# USB_RF_Gateway_v_0_1.net
KiCad netlist of a schematic drawn in EAGLE
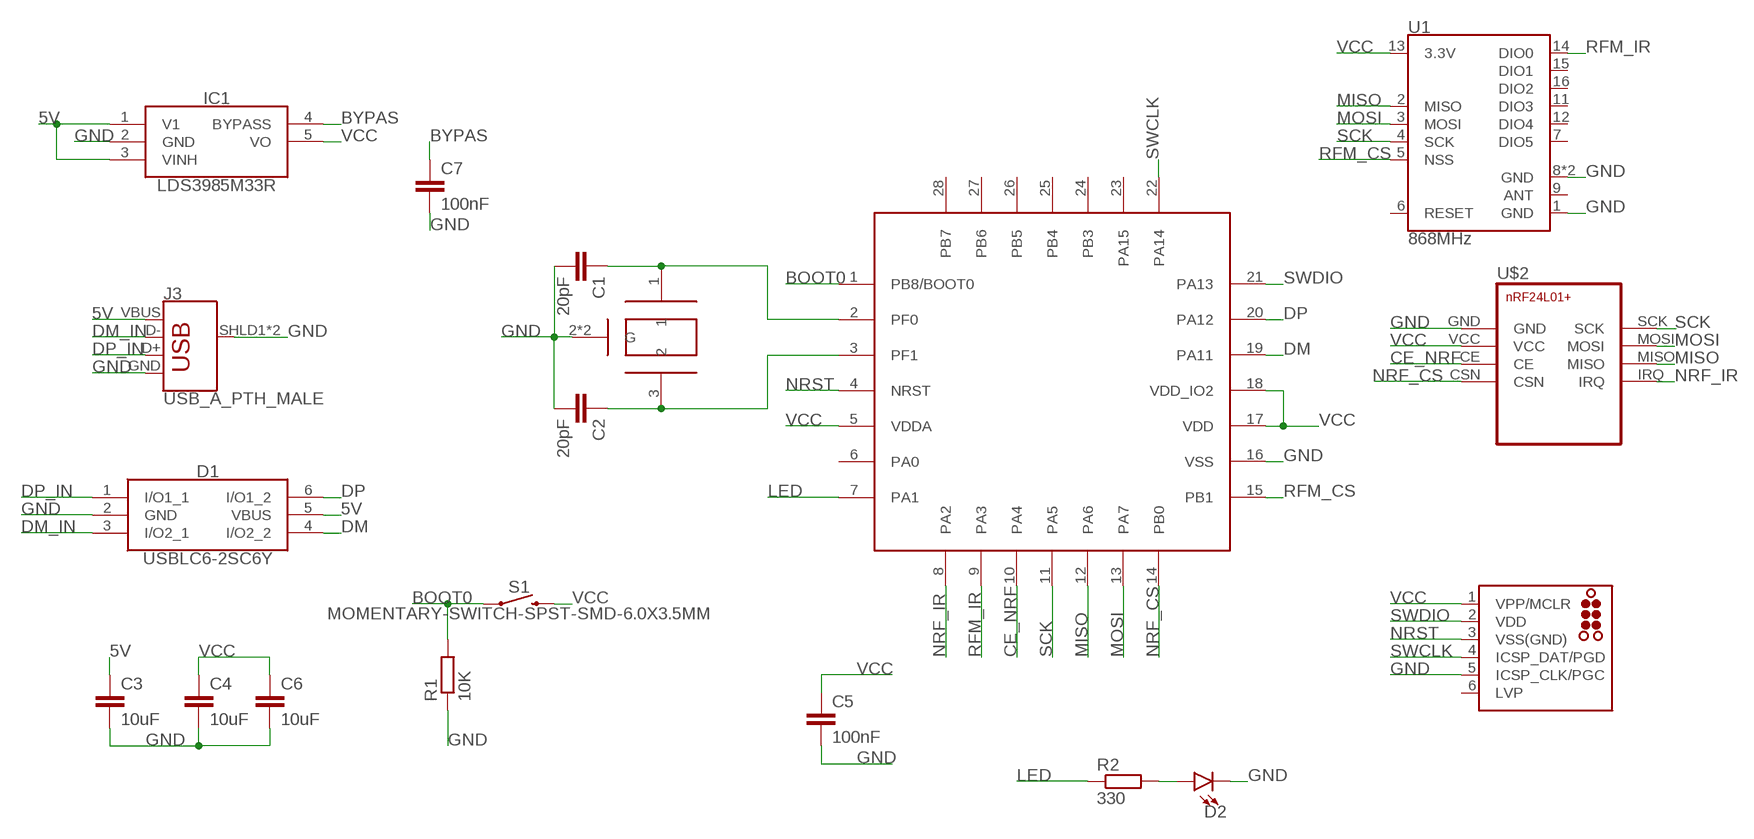
[diagram p0: schematic, sheet 1]

(export (version "E")
  (design (tool "Eeschema 10.0.6"))
  (components
    (comp (ref "C1")
      (value "20pF")
      (footprint "eagle-import:C0603")
      (libsource (lib "eagle-import") (part "C-EUC0603"))
    )
    (comp (ref "C2")
      (value "20pF")
      (footprint "eagle-import:C0603")
      (libsource (lib "eagle-import") (part "C-EUC0603"))
    )
    (comp (ref "C3")
      (value "10uF")
      (footprint "eagle-import:C0805")
      (libsource (lib "eagle-import") (part "C-EUC0805"))
    )
    (comp (ref "C4")
      (value "10uF")
      (footprint "eagle-import:C0805")
      (libsource (lib "eagle-import") (part "C-EUC0805"))
    )
    (comp (ref "C5")
      (value "100nF")
      (footprint "eagle-import:C0603")
      (libsource (lib "eagle-import") (part "C-EUC0603"))
    )
    (comp (ref "C6")
      (value "10uF")
      (footprint "eagle-import:C0805")
      (libsource (lib "eagle-import") (part "C-EUC0805"))
    )
    (comp (ref "C7")
      (value "100nF")
      (footprint "eagle-import:C0603")
      (libsource (lib "eagle-import") (part "C-EUC0603"))
    )
    (comp (ref "D1")
      (value "USBLC6-2SC6Y")
      (footprint "eagle-import:SOT95P280X145-6N")
      (fields
        (field (name "MOUSER_PART_NUMBER") "511-USBLC6-2SC6Y")
        (field (name "RS_PART_NUMBER") "8805525P")
      )
      (libsource (lib "eagle-import") (part "USBLC6-2SC6Y"))
    )
    (comp (ref "D2")
      (value "LED0603")
      (footprint "eagle-import:LED-0603")
      (libsource (lib "eagle-import") (part "LED0603"))
    )
    (comp (ref "IC1")
      (value "LDS3985M33R")
      (footprint "eagle-import:SOT95P280X145-5N")
      (fields
        (field (name "MOUSER_PART_NUMBER") "511-LDS3985M33R")
        (field (name "RS_PART_NUMBER") "8805323P")
      )
      (libsource (lib "eagle-import") (part "LDS3985M33R"))
    )
    (comp (ref "J2")
      (value "TC2030-MCP-NL")
      (footprint "eagle-import:TC2030-MCP-NL")
      (libsource (lib "eagle-import") (part "TC2030-MCP-NL"))
    )
    (comp (ref "J3")
      (value "USB_A_PTH_MALE")
      (footprint "eagle-import:USB-A-H")
      (libsource (lib "eagle-import") (part "USB_A_PTH_MALE"))
    )
    (comp (ref "R1")
      (value "10K")
      (footprint "eagle-import:R0603")
      (libsource (lib "eagle-import") (part "R-EU_R0603"))
    )
    (comp (ref "R2")
      (value "330")
      (footprint "eagle-import:R0603")
      (libsource (lib "eagle-import") (part "R-EU_R0603"))
    )
    (comp (ref "S1")
      (value "MOMENTARY-SWITCH-SPST-SMD-6.0X3.5MM")
      (footprint "eagle-import:TACTILE_SWITCH_SMD_6.0X3.5MM")
      (libsource (lib "eagle-import") (part "MOMENTARY-SWITCH-SPST-SMD-6.0X3.5MM"))
    )
    (comp (ref "U$1")
      (value "ECS-160-12-37B-CTN-TR")
      (footprint "eagle-import:ECS-160-12-37B-CTN")
      (libsource (lib "eagle-import") (part "ECS-160-12-37B-CTN-TR"))
    )
    (comp (ref "U$2")
      (value "NRF24L01+NRF24L01+MINI")
      (footprint "eagle-import:NRF24L01+MINI")
      (libsource (lib "eagle-import") (part "NRF24L01+NRF24L01+MINI"))
    )
    (comp (ref "U$3")
      (value "STMF042G6U6")
      (footprint "eagle-import:STM32F042_UFQPN28_4X4MM")
      (libsource (lib "eagle-import") (part "STMF042G6U6"))
    )
    (comp (ref "U1")
      (value "868MHz")
      (footprint "eagle-import:RFM69HCW-XXXS2")
      (libsource (lib "eagle-import") (part "RFM69HCW-915"))
    )
  )
  (nets
    (net (code "1") (name "/5V") (class "Default")
      (node (ref "C3") (pin "1") (pinfunction "1_1") (pintype "passive"))
      (node (ref "D1") (pin "5") (pinfunction "VBUS_5") (pintype "bidirectional"))
      (node (ref "IC1") (pin "1") (pinfunction "V1_1") (pintype "bidirectional"))
      (node (ref "IC1") (pin "3") (pinfunction "VINH_3") (pintype "bidirectional"))
      (node (ref "J3") (pin "VBUS") (pinfunction "VBUS_VBUS") (pintype "power_in"))
    )
    (net (code "2") (name "/BOOT0") (class "Default")
      (node (ref "R1") (pin "2") (pinfunction "2_2") (pintype "passive"))
      (node (ref "S1") (pin "1") (pinfunction "1_1") (pintype "passive"))
      (node (ref "U$3") (pin "1") (pinfunction "PB8/BOOT0_1") (pintype "bidirectional"))
    )
    (net (code "3") (name "/BYPAS") (class "Default")
      (node (ref "C7") (pin "1") (pinfunction "1_1") (pintype "passive"))
      (node (ref "IC1") (pin "4") (pinfunction "BYPASS_4") (pintype "bidirectional"))
    )
    (net (code "4") (name "/CE_NRF") (class "Default")
      (node (ref "U$2") (pin "CE") (pinfunction "CE_CE") (pintype "bidirectional"))
      (node (ref "U$3") (pin "10") (pinfunction "PA4_10") (pintype "bidirectional"))
    )
    (net (code "5") (name "/DM") (class "Default")
      (node (ref "D1") (pin "4") (pinfunction "I/O2_2_4") (pintype "bidirectional"))
      (node (ref "U$3") (pin "19") (pinfunction "PA11_19") (pintype "bidirectional"))
    )
    (net (code "6") (name "/DM_IN") (class "Default")
      (node (ref "D1") (pin "3") (pinfunction "I/O2_1_3") (pintype "bidirectional"))
      (node (ref "J3") (pin "D-") (pinfunction "D-_D-") (pintype "bidirectional"))
    )
    (net (code "7") (name "/DP") (class "Default")
      (node (ref "D1") (pin "6") (pinfunction "I/O1_2_6") (pintype "bidirectional"))
      (node (ref "U$3") (pin "20") (pinfunction "PA12_20") (pintype "bidirectional"))
    )
    (net (code "8") (name "/DP_IN") (class "Default")
      (node (ref "D1") (pin "1") (pinfunction "I/O1_1_1") (pintype "bidirectional"))
      (node (ref "J3") (pin "D+") (pinfunction "D+_D+") (pintype "bidirectional"))
    )
    (net (code "9") (name "/GND") (class "Default")
      (node (ref "C1") (pin "2") (pinfunction "2_2") (pintype "passive"))
      (node (ref "C2") (pin "2") (pinfunction "2_2") (pintype "passive"))
      (node (ref "C3") (pin "2") (pinfunction "2_2") (pintype "passive"))
      (node (ref "C4") (pin "2") (pinfunction "2_2") (pintype "passive"))
      (node (ref "C5") (pin "2") (pinfunction "2_2") (pintype "passive"))
      (node (ref "C6") (pin "2") (pinfunction "2_2") (pintype "passive"))
      (node (ref "C7") (pin "2") (pinfunction "2_2") (pintype "passive"))
      (node (ref "D1") (pin "2") (pinfunction "GND_2") (pintype "bidirectional"))
      (node (ref "D2") (pin "C") (pinfunction "C_C") (pintype "passive"))
      (node (ref "IC1") (pin "2") (pinfunction "GND_2") (pintype "bidirectional"))
      (node (ref "J2") (pin "5") (pinfunction "ICSP_CLK/PGC_5") (pintype "output"))
      (node (ref "J3") (pin "GND") (pinfunction "GND_GND") (pintype "power_in"))
      (node (ref "J3") (pin "SHLD1") (pinfunction "SHIELD_SHLD1") (pintype "bidirectional"))
      (node (ref "J3") (pin "SHLD2") (pinfunction "SHIELD_SHLD2") (pintype "bidirectional"))
      (node (ref "R1") (pin "1") (pinfunction "1_1") (pintype "passive"))
      (node (ref "U$1") (pin "2") (pinfunction "G_2") (pintype "bidirectional"))
      (node (ref "U$1") (pin "4") (pinfunction "G_4") (pintype "bidirectional"))
      (node (ref "U$2") (pin "GND") (pinfunction "GND_GND") (pintype "power_in"))
      (node (ref "U$3") (pin "16") (pinfunction "VSS_16") (pintype "bidirectional"))
      (node (ref "U1") (pin "1") (pinfunction "GND_1") (pintype "power_in"))
      (node (ref "U1") (pin "10") (pinfunction "GND_10") (pintype "power_in"))
      (node (ref "U1") (pin "8") (pinfunction "GND_8") (pintype "power_in"))
    )
    (net (code "10") (name "/LED") (class "Default")
      (node (ref "R2") (pin "1") (pinfunction "1_1") (pintype "passive"))
      (node (ref "U$3") (pin "7") (pinfunction "PA1_7") (pintype "bidirectional"))
    )
    (net (code "11") (name "/MISO") (class "Default")
      (node (ref "U$2") (pin "MISO") (pinfunction "MISO_MISO") (pintype "bidirectional"))
      (node (ref "U$3") (pin "12") (pinfunction "PA6_12") (pintype "bidirectional"))
      (node (ref "U1") (pin "2") (pinfunction "MISO_2") (pintype "bidirectional"))
    )
    (net (code "12") (name "/MOSI") (class "Default")
      (node (ref "U$2") (pin "MOSI") (pinfunction "MOSI_MOSI") (pintype "bidirectional"))
      (node (ref "U$3") (pin "13") (pinfunction "PA7_13") (pintype "bidirectional"))
      (node (ref "U1") (pin "3") (pinfunction "MOSI_3") (pintype "input"))
    )
    (net (code "13") (name "/NRF_CS") (class "Default")
      (node (ref "U$2") (pin "CSN") (pinfunction "CSN_CSN") (pintype "bidirectional"))
      (node (ref "U$3") (pin "14") (pinfunction "PB0_14") (pintype "bidirectional"))
    )
    (net (code "14") (name "/NRF_IR") (class "Default")
      (node (ref "U$2") (pin "IRQ") (pinfunction "IRQ_IRQ") (pintype "bidirectional"))
      (node (ref "U$3") (pin "8") (pinfunction "PA2_8") (pintype "bidirectional"))
    )
    (net (code "15") (name "/NRST") (class "Default")
      (node (ref "J2") (pin "3") (pinfunction "VSS(GND)_3") (pintype "power_in"))
      (node (ref "U$3") (pin "4") (pinfunction "NRST_4") (pintype "bidirectional"))
    )
    (net (code "16") (name "/RFM_CS") (class "Default")
      (node (ref "U$3") (pin "15") (pinfunction "PB1_15") (pintype "bidirectional"))
      (node (ref "U1") (pin "5") (pinfunction "NSS_5") (pintype "input"))
    )
    (net (code "17") (name "/RFM_IR") (class "Default")
      (node (ref "U$3") (pin "9") (pinfunction "PA3_9") (pintype "bidirectional"))
      (node (ref "U1") (pin "14") (pinfunction "DIO0_14") (pintype "bidirectional"))
    )
    (net (code "18") (name "/SCK") (class "Default")
      (node (ref "U$2") (pin "SCK") (pinfunction "SCK_SCK") (pintype "bidirectional"))
      (node (ref "U$3") (pin "11") (pinfunction "PA5_11") (pintype "bidirectional"))
      (node (ref "U1") (pin "4") (pinfunction "SCK_4") (pintype "input"))
    )
    (net (code "19") (name "/SWCLK") (class "Default")
      (node (ref "J2") (pin "4") (pinfunction "ICSP_DAT/PGD_4") (pintype "bidirectional"))
      (node (ref "U$3") (pin "22") (pinfunction "PA14_22") (pintype "bidirectional"))
    )
    (net (code "20") (name "/SWDIO") (class "Default")
      (node (ref "J2") (pin "2") (pinfunction "VDD_2") (pintype "power_in"))
      (node (ref "U$3") (pin "21") (pinfunction "PA13_21") (pintype "bidirectional"))
    )
    (net (code "21") (name "/VCC") (class "Default")
      (node (ref "C4") (pin "1") (pinfunction "1_1") (pintype "passive"))
      (node (ref "C5") (pin "1") (pinfunction "1_1") (pintype "passive"))
      (node (ref "C6") (pin "1") (pinfunction "1_1") (pintype "passive"))
      (node (ref "IC1") (pin "5") (pinfunction "VO_5") (pintype "bidirectional"))
      (node (ref "J2") (pin "1") (pinfunction "VPP/MCLR_1") (pintype "passive"))
      (node (ref "S1") (pin "2") (pinfunction "2_2") (pintype "passive"))
      (node (ref "U$2") (pin "VCC") (pinfunction "VCC_VCC") (pintype "power_in"))
      (node (ref "U$3") (pin "17") (pinfunction "VDD_17") (pintype "bidirectional"))
      (node (ref "U$3") (pin "18") (pinfunction "VDD_IO2_18") (pintype "bidirectional"))
      (node (ref "U$3") (pin "5") (pinfunction "VDDA_5") (pintype "bidirectional"))
      (node (ref "U1") (pin "13") (pinfunction "3.3V_13") (pintype "power_in"))
    )
    (net (code "22") (name "Net-(D2-PadA)") (class "Default")
      (node (ref "D2") (pin "A") (pinfunction "A_A") (pintype "passive"))
      (node (ref "R2") (pin "2") (pinfunction "2_2") (pintype "passive"))
    )
    (net (code "23") (name "Net-(U$1-2)") (class "Default")
      (node (ref "C2") (pin "1") (pinfunction "1_1") (pintype "passive"))
      (node (ref "U$1") (pin "3") (pinfunction "2_3") (pintype "bidirectional"))
      (node (ref "U$3") (pin "3") (pinfunction "PF1_3") (pintype "bidirectional"))
    )
    (net (code "24") (name "Net-(U$3-PF0)") (class "Default")
      (node (ref "C1") (pin "1") (pinfunction "1_1") (pintype "passive"))
      (node (ref "U$1") (pin "1") (pinfunction "1_1") (pintype "bidirectional"))
      (node (ref "U$3") (pin "2") (pinfunction "PF0_2") (pintype "bidirectional"))
    )
    (net (code "25") (name "unconnected-(J2-LVP-Pad6)") (class "Default")
      (node (ref "J2") (pin "6") (pinfunction "LVP_6") (pintype "bidirectional"))
    )
    (net (code "26") (name "unconnected-(U$3-PA0-Pad6)") (class "Default")
      (node (ref "U$3") (pin "6") (pinfunction "PA0_6") (pintype "bidirectional"))
    )
    (net (code "27") (name "unconnected-(U$3-PA15-Pad23)") (class "Default")
      (node (ref "U$3") (pin "23") (pinfunction "PA15_23") (pintype "bidirectional"))
    )
    (net (code "28") (name "unconnected-(U$3-PB3-Pad24)") (class "Default")
      (node (ref "U$3") (pin "24") (pinfunction "PB3_24") (pintype "bidirectional"))
    )
    (net (code "29") (name "unconnected-(U$3-PB4-Pad25)") (class "Default")
      (node (ref "U$3") (pin "25") (pinfunction "PB4_25") (pintype "bidirectional"))
    )
    (net (code "30") (name "unconnected-(U$3-PB5-Pad26)") (class "Default")
      (node (ref "U$3") (pin "26") (pinfunction "PB5_26") (pintype "bidirectional"))
    )
    (net (code "31") (name "unconnected-(U$3-PB6-Pad27)") (class "Default")
      (node (ref "U$3") (pin "27") (pinfunction "PB6_27") (pintype "bidirectional"))
    )
    (net (code "32") (name "unconnected-(U$3-PB7-Pad28)") (class "Default")
      (node (ref "U$3") (pin "28") (pinfunction "PB7_28") (pintype "bidirectional"))
    )
    (net (code "33") (name "unconnected-(U1-ANT-Pad9)") (class "Default")
      (node (ref "U1") (pin "9") (pinfunction "ANT_9") (pintype "passive"))
    )
    (net (code "34") (name "unconnected-(U1-DIO1-Pad15)") (class "Default")
      (node (ref "U1") (pin "15") (pinfunction "DIO1_15") (pintype "bidirectional"))
    )
    (net (code "35") (name "unconnected-(U1-DIO2-Pad16)") (class "Default")
      (node (ref "U1") (pin "16") (pinfunction "DIO2_16") (pintype "bidirectional"))
    )
    (net (code "36") (name "unconnected-(U1-DIO3-Pad11)") (class "Default")
      (node (ref "U1") (pin "11") (pinfunction "DIO3_11") (pintype "bidirectional"))
    )
    (net (code "37") (name "unconnected-(U1-DIO4-Pad12)") (class "Default")
      (node (ref "U1") (pin "12") (pinfunction "DIO4_12") (pintype "bidirectional"))
    )
    (net (code "38") (name "unconnected-(U1-DIO5-Pad7)") (class "Default")
      (node (ref "U1") (pin "7") (pinfunction "DIO5_7") (pintype "bidirectional"))
    )
    (net (code "39") (name "unconnected-(U1-RESET-Pad6)") (class "Default")
      (node (ref "U1") (pin "6") (pinfunction "RESET_6") (pintype "input"))
    )
  )
)
